# Main_Circuit.net
KiCad netlist of a schematic drawn in EAGLE
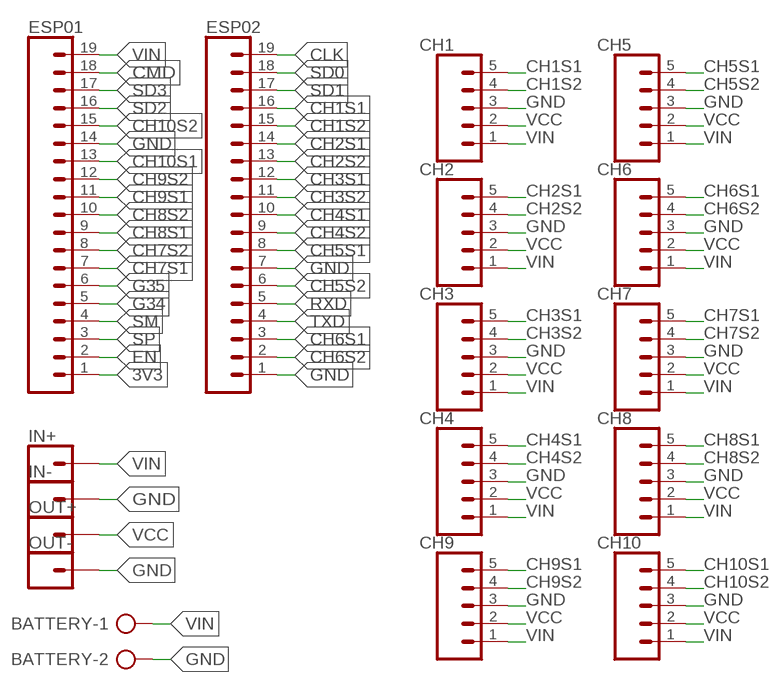
[diagram p0: schematic, sheet 1]

(export (version "E")
  (design (tool "Eeschema 10.0.6"))
  (components
    (comp (ref "BATTERY")
      (value "AK500/2-H")
      (footprint "eagle-import:AK500_2-H")
      (libsource (lib "eagle-import") (part "AK500/2-H"))
    )
    (comp (ref "CH1")
      (value "CONN_05")
      (footprint "eagle-import:1X05")
      (libsource (lib "eagle-import") (part "CONN_05"))
    )
    (comp (ref "CH2")
      (value "CONN_05")
      (footprint "eagle-import:1X05")
      (libsource (lib "eagle-import") (part "CONN_05"))
    )
    (comp (ref "CH3")
      (value "CONN_05")
      (footprint "eagle-import:1X05")
      (libsource (lib "eagle-import") (part "CONN_05"))
    )
    (comp (ref "CH4")
      (value "CONN_05")
      (footprint "eagle-import:1X05")
      (libsource (lib "eagle-import") (part "CONN_05"))
    )
    (comp (ref "CH5")
      (value "CONN_05")
      (footprint "eagle-import:1X05")
      (libsource (lib "eagle-import") (part "CONN_05"))
    )
    (comp (ref "CH6")
      (value "CONN_05")
      (footprint "eagle-import:1X05")
      (libsource (lib "eagle-import") (part "CONN_05"))
    )
    (comp (ref "CH7")
      (value "CONN_05")
      (footprint "eagle-import:1X05")
      (libsource (lib "eagle-import") (part "CONN_05"))
    )
    (comp (ref "CH8")
      (value "CONN_05")
      (footprint "eagle-import:1X05")
      (libsource (lib "eagle-import") (part "CONN_05"))
    )
    (comp (ref "CH9")
      (value "CONN_05")
      (footprint "eagle-import:1X05")
      (libsource (lib "eagle-import") (part "CONN_05"))
    )
    (comp (ref "CH10")
      (value "CONN_05")
      (footprint "eagle-import:1X05")
      (libsource (lib "eagle-import") (part "CONN_05"))
    )
    (comp (ref "ESP01")
      (value "CONN_19")
      (footprint "eagle-import:1X19")
      (libsource (lib "eagle-import") (part "CONN_19"))
    )
    (comp (ref "ESP02")
      (value "CONN_19")
      (footprint "eagle-import:1X19")
      (libsource (lib "eagle-import") (part "CONN_19"))
    )
    (comp (ref "IN+")
      (value "CONN_01")
      (footprint "eagle-import:1X01")
      (libsource (lib "eagle-import") (part "CONN_01"))
    )
    (comp (ref "IN-")
      (value "CONN_01")
      (footprint "eagle-import:1X01")
      (libsource (lib "eagle-import") (part "CONN_01"))
    )
    (comp (ref "OUT+")
      (value "CONN_01")
      (footprint "eagle-import:1X01")
      (libsource (lib "eagle-import") (part "CONN_01"))
    )
    (comp (ref "OUT-")
      (value "CONN_01")
      (footprint "eagle-import:1X01")
      (libsource (lib "eagle-import") (part "CONN_01"))
    )
  )
  (nets
    (net (code "1") (name "3V3") (class "Default")
      (node (ref "ESP01") (pin "1") (pinfunction "1_1") (pintype "passive"))
    )
    (net (code "2") (name "CH1S1") (class "Default")
      (node (ref "CH1") (pin "5") (pinfunction "5_5") (pintype "passive"))
      (node (ref "ESP02") (pin "16") (pinfunction "16_16") (pintype "passive"))
    )
    (net (code "3") (name "CH1S2") (class "Default")
      (node (ref "CH1") (pin "4") (pinfunction "4_4") (pintype "passive"))
      (node (ref "ESP02") (pin "15") (pinfunction "15_15") (pintype "passive"))
    )
    (net (code "4") (name "CH2S1") (class "Default")
      (node (ref "CH2") (pin "5") (pinfunction "5_5") (pintype "passive"))
      (node (ref "ESP02") (pin "14") (pinfunction "14_14") (pintype "passive"))
    )
    (net (code "5") (name "CH2S2") (class "Default")
      (node (ref "CH2") (pin "4") (pinfunction "4_4") (pintype "passive"))
      (node (ref "ESP02") (pin "13") (pinfunction "13_13") (pintype "passive"))
    )
    (net (code "6") (name "CH3S1") (class "Default")
      (node (ref "CH3") (pin "5") (pinfunction "5_5") (pintype "passive"))
      (node (ref "ESP02") (pin "12") (pinfunction "12_12") (pintype "passive"))
    )
    (net (code "7") (name "CH3S2") (class "Default")
      (node (ref "CH3") (pin "4") (pinfunction "4_4") (pintype "passive"))
      (node (ref "ESP02") (pin "11") (pinfunction "11_11") (pintype "passive"))
    )
    (net (code "8") (name "CH4S1") (class "Default")
      (node (ref "CH4") (pin "5") (pinfunction "5_5") (pintype "passive"))
      (node (ref "ESP02") (pin "10") (pinfunction "10_10") (pintype "passive"))
    )
    (net (code "9") (name "CH4S2") (class "Default")
      (node (ref "CH4") (pin "4") (pinfunction "4_4") (pintype "passive"))
      (node (ref "ESP02") (pin "9") (pinfunction "9_9") (pintype "passive"))
    )
    (net (code "10") (name "CH5S1") (class "Default")
      (node (ref "CH5") (pin "5") (pinfunction "5_5") (pintype "passive"))
      (node (ref "ESP02") (pin "8") (pinfunction "8_8") (pintype "passive"))
    )
    (net (code "11") (name "CH5S2") (class "Default")
      (node (ref "CH5") (pin "4") (pinfunction "4_4") (pintype "passive"))
      (node (ref "ESP02") (pin "6") (pinfunction "6_6") (pintype "passive"))
    )
    (net (code "12") (name "CH6S1") (class "Default")
      (node (ref "CH6") (pin "5") (pinfunction "5_5") (pintype "passive"))
      (node (ref "ESP02") (pin "3") (pinfunction "3_3") (pintype "passive"))
    )
    (net (code "13") (name "CH6S2") (class "Default")
      (node (ref "CH6") (pin "4") (pinfunction "4_4") (pintype "passive"))
      (node (ref "ESP02") (pin "2") (pinfunction "2_2") (pintype "passive"))
    )
    (net (code "14") (name "CH7S1") (class "Default")
      (node (ref "CH7") (pin "5") (pinfunction "5_5") (pintype "passive"))
      (node (ref "ESP01") (pin "7") (pinfunction "7_7") (pintype "passive"))
    )
    (net (code "15") (name "CH7S2") (class "Default")
      (node (ref "CH7") (pin "4") (pinfunction "4_4") (pintype "passive"))
      (node (ref "ESP01") (pin "8") (pinfunction "8_8") (pintype "passive"))
    )
    (net (code "16") (name "CH8S1") (class "Default")
      (node (ref "CH8") (pin "5") (pinfunction "5_5") (pintype "passive"))
      (node (ref "ESP01") (pin "9") (pinfunction "9_9") (pintype "passive"))
    )
    (net (code "17") (name "CH8S2") (class "Default")
      (node (ref "CH8") (pin "4") (pinfunction "4_4") (pintype "passive"))
      (node (ref "ESP01") (pin "10") (pinfunction "10_10") (pintype "passive"))
    )
    (net (code "18") (name "CH9S1") (class "Default")
      (node (ref "CH9") (pin "5") (pinfunction "5_5") (pintype "passive"))
      (node (ref "ESP01") (pin "11") (pinfunction "11_11") (pintype "passive"))
    )
    (net (code "19") (name "CH9S2") (class "Default")
      (node (ref "CH9") (pin "4") (pinfunction "4_4") (pintype "passive"))
      (node (ref "ESP01") (pin "12") (pinfunction "12_12") (pintype "passive"))
    )
    (net (code "20") (name "CH10S1") (class "Default")
      (node (ref "CH10") (pin "5") (pinfunction "5_5") (pintype "passive"))
      (node (ref "ESP01") (pin "13") (pinfunction "13_13") (pintype "passive"))
    )
    (net (code "21") (name "CH10S2") (class "Default")
      (node (ref "CH10") (pin "4") (pinfunction "4_4") (pintype "passive"))
      (node (ref "ESP01") (pin "15") (pinfunction "15_15") (pintype "passive"))
    )
    (net (code "22") (name "CLK") (class "Default")
      (node (ref "ESP02") (pin "19") (pinfunction "19_19") (pintype "passive"))
    )
    (net (code "23") (name "CMD") (class "Default")
      (node (ref "ESP01") (pin "18") (pinfunction "18_18") (pintype "passive"))
    )
    (net (code "24") (name "EN") (class "Default")
      (node (ref "ESP01") (pin "2") (pinfunction "2_2") (pintype "passive"))
    )
    (net (code "25") (name "G34") (class "Default")
      (node (ref "ESP01") (pin "5") (pinfunction "5_5") (pintype "passive"))
    )
    (net (code "26") (name "G35") (class "Default")
      (node (ref "ESP01") (pin "6") (pinfunction "6_6") (pintype "passive"))
    )
    (net (code "27") (name "GND") (class "Default")
      (node (ref "BATTERY") (pin "2") (pinfunction "KL_2") (pintype "passive"))
      (node (ref "CH1") (pin "3") (pinfunction "3_3") (pintype "passive"))
      (node (ref "CH10") (pin "3") (pinfunction "3_3") (pintype "passive"))
      (node (ref "CH2") (pin "3") (pinfunction "3_3") (pintype "passive"))
      (node (ref "CH3") (pin "3") (pinfunction "3_3") (pintype "passive"))
      (node (ref "CH4") (pin "3") (pinfunction "3_3") (pintype "passive"))
      (node (ref "CH5") (pin "3") (pinfunction "3_3") (pintype "passive"))
      (node (ref "CH6") (pin "3") (pinfunction "3_3") (pintype "passive"))
      (node (ref "CH7") (pin "3") (pinfunction "3_3") (pintype "passive"))
      (node (ref "CH8") (pin "3") (pinfunction "3_3") (pintype "passive"))
      (node (ref "CH9") (pin "3") (pinfunction "3_3") (pintype "passive"))
      (node (ref "ESP01") (pin "14") (pinfunction "14_14") (pintype "passive"))
      (node (ref "ESP02") (pin "1") (pinfunction "1_1") (pintype "passive"))
      (node (ref "ESP02") (pin "7") (pinfunction "7_7") (pintype "passive"))
      (node (ref "IN-") (pin "1") (pinfunction "1_1") (pintype "passive"))
      (node (ref "OUT-") (pin "1") (pinfunction "1_1") (pintype "passive"))
    )
    (net (code "28") (name "RXD") (class "Default")
      (node (ref "ESP02") (pin "5") (pinfunction "5_5") (pintype "passive"))
    )
    (net (code "29") (name "SD0") (class "Default")
      (node (ref "ESP02") (pin "18") (pinfunction "18_18") (pintype "passive"))
    )
    (net (code "30") (name "SD1") (class "Default")
      (node (ref "ESP02") (pin "17") (pinfunction "17_17") (pintype "passive"))
    )
    (net (code "31") (name "SD2") (class "Default")
      (node (ref "ESP01") (pin "16") (pinfunction "16_16") (pintype "passive"))
    )
    (net (code "32") (name "SD3") (class "Default")
      (node (ref "ESP01") (pin "17") (pinfunction "17_17") (pintype "passive"))
    )
    (net (code "33") (name "SM") (class "Default")
      (node (ref "ESP01") (pin "4") (pinfunction "4_4") (pintype "passive"))
    )
    (net (code "34") (name "SP") (class "Default")
      (node (ref "ESP01") (pin "3") (pinfunction "3_3") (pintype "passive"))
    )
    (net (code "35") (name "TXD") (class "Default")
      (node (ref "ESP02") (pin "4") (pinfunction "4_4") (pintype "passive"))
    )
    (net (code "36") (name "VCC") (class "Default")
      (node (ref "CH1") (pin "2") (pinfunction "2_2") (pintype "passive"))
      (node (ref "CH10") (pin "2") (pinfunction "2_2") (pintype "passive"))
      (node (ref "CH2") (pin "2") (pinfunction "2_2") (pintype "passive"))
      (node (ref "CH3") (pin "2") (pinfunction "2_2") (pintype "passive"))
      (node (ref "CH4") (pin "2") (pinfunction "2_2") (pintype "passive"))
      (node (ref "CH5") (pin "2") (pinfunction "2_2") (pintype "passive"))
      (node (ref "CH6") (pin "2") (pinfunction "2_2") (pintype "passive"))
      (node (ref "CH7") (pin "2") (pinfunction "2_2") (pintype "passive"))
      (node (ref "CH8") (pin "2") (pinfunction "2_2") (pintype "passive"))
      (node (ref "CH9") (pin "2") (pinfunction "2_2") (pintype "passive"))
      (node (ref "OUT+") (pin "1") (pinfunction "1_1") (pintype "passive"))
    )
    (net (code "37") (name "VIN") (class "Default")
      (node (ref "BATTERY") (pin "1") (pinfunction "KL_1") (pintype "passive"))
      (node (ref "CH1") (pin "1") (pinfunction "1_1") (pintype "passive"))
      (node (ref "CH10") (pin "1") (pinfunction "1_1") (pintype "passive"))
      (node (ref "CH2") (pin "1") (pinfunction "1_1") (pintype "passive"))
      (node (ref "CH3") (pin "1") (pinfunction "1_1") (pintype "passive"))
      (node (ref "CH4") (pin "1") (pinfunction "1_1") (pintype "passive"))
      (node (ref "CH5") (pin "1") (pinfunction "1_1") (pintype "passive"))
      (node (ref "CH6") (pin "1") (pinfunction "1_1") (pintype "passive"))
      (node (ref "CH7") (pin "1") (pinfunction "1_1") (pintype "passive"))
      (node (ref "CH8") (pin "1") (pinfunction "1_1") (pintype "passive"))
      (node (ref "CH9") (pin "1") (pinfunction "1_1") (pintype "passive"))
      (node (ref "ESP01") (pin "19") (pinfunction "19_19") (pintype "passive"))
      (node (ref "IN+") (pin "1") (pinfunction "1_1") (pintype "passive"))
    )
  )
)
